# TPS54331_1A.net
KiCad netlist of a schematic drawn in Altium Designer
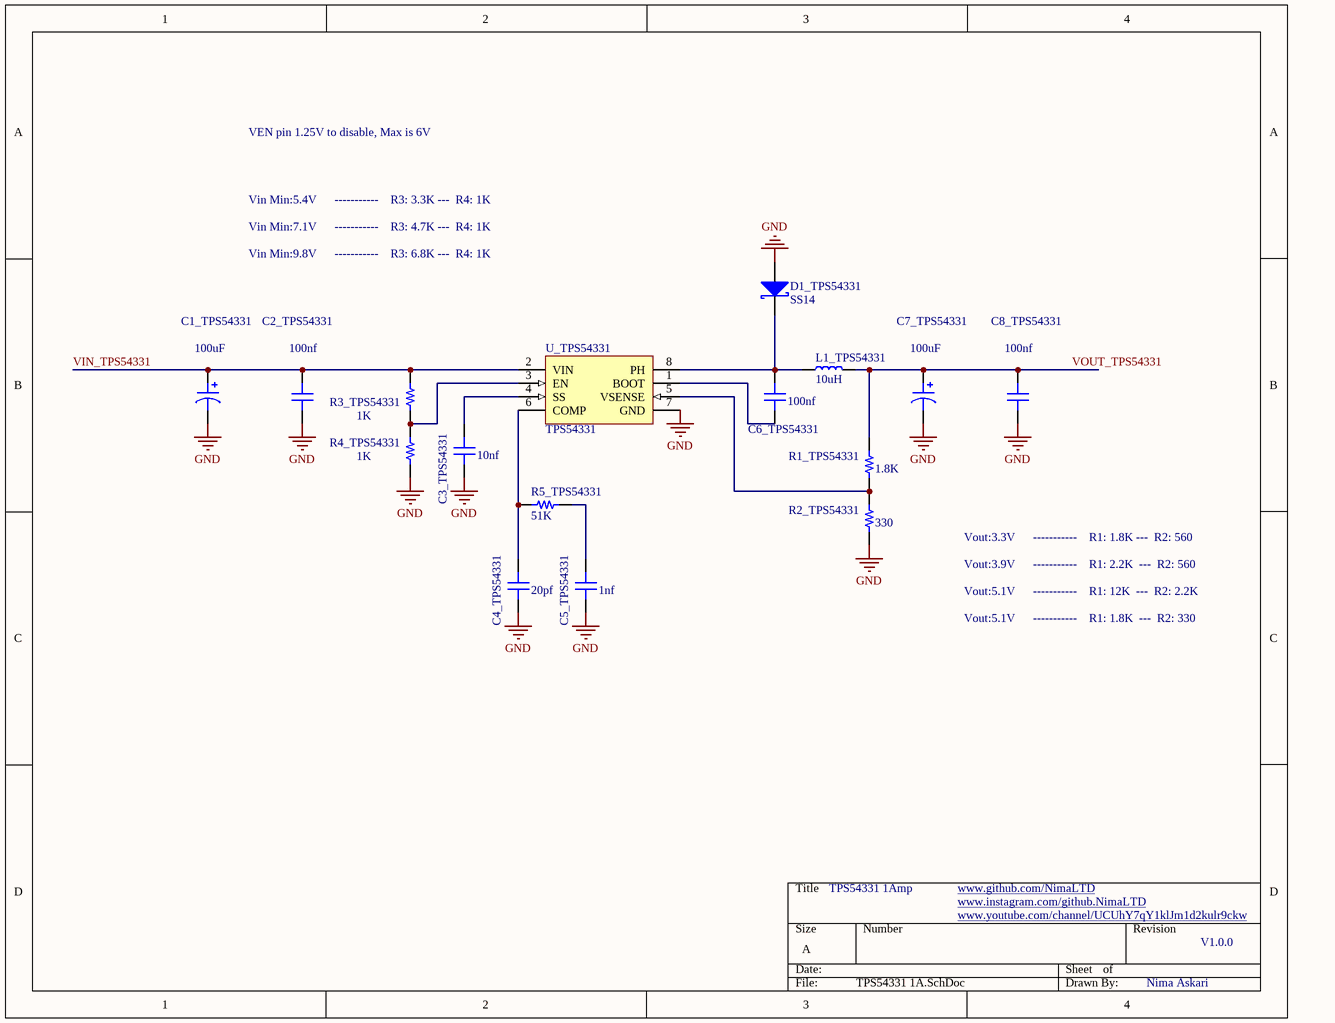
[diagram p0: TPS54331 1A.SchDoc]

(export (version "E")
  (design (tool "Eeschema 10.0.6"))
  (components
    (comp (ref "C1_TPS54331")
      (value "100uF")
      (footprint "CAP AL SMD D6 H6")
      (description "SMT Polarised Capacitor")
      (libsource (lib "CAPACITOR") (part "Pol Cap SMD AL D6 H6"))
    )
    (comp (ref "C2_TPS54331")
      (value "100nf")
      (footprint "CAP 1206")
      (description "SMT Capacitor")
      (libsource (lib "CAPACITOR") (part "Cap SMD 1206"))
    )
    (comp (ref "C3_TPS54331")
      (value "10nf")
      (footprint "CAP 0805")
      (description "SMT Capacitor")
      (libsource (lib "CAPACITOR") (part "Cap SMD 0805"))
    )
    (comp (ref "C4_TPS54331")
      (value "20pf")
      (footprint "CAP 0805")
      (description "SMT Capacitor")
      (libsource (lib "CAPACITOR") (part "Cap SMD 0805"))
    )
    (comp (ref "C5_TPS54331")
      (value "1nf")
      (footprint "CAP 0805")
      (description "SMT Capacitor")
      (libsource (lib "CAPACITOR") (part "Cap SMD 0805"))
    )
    (comp (ref "C6_TPS54331")
      (value "100nf")
      (footprint "CAP 0805")
      (description "SMT Capacitor")
      (libsource (lib "CAPACITOR") (part "Cap SMD 0805"))
    )
    (comp (ref "C7_TPS54331")
      (value "100uF")
      (footprint "CAP AL SMD D6 H6")
      (description "SMT Polarised Capacitor")
      (libsource (lib "CAPACITOR") (part "Pol Cap SMD AL D6 H6"))
    )
    (comp (ref "C8_TPS54331")
      (value "100nf")
      (footprint "CAP 0805")
      (description "SMT Capacitor")
      (libsource (lib "CAPACITOR") (part "Cap SMD 0805"))
    )
    (comp (ref "D1_TPS54331")
      (value "SS14 SMD")
      (footprint "DO214AC SMA")
      (description "1A Schottky")
      (fields (field (name "PARAMETER 1") "SS14"))
      (libsource (lib "DIODE") (part "SS14 SMD"))
    )
    (comp (ref "L1_TPS54331")
      (value "10uH")
      (footprint "IND 7X7")
      (description "SMT Inductor")
      (fields (field (name "Comment") "Inductor SMD POWER 7X7mm"))
      (libsource (lib "INDUCTOR") (part "Inductor SMD POWER 7X7mm"))
    )
    (comp (ref "R1_TPS54331")
      (value "1.8K")
      (footprint "RES 0805")
      (description "SMD Resistor")
      (libsource (lib "RESISTOR") (part "Res SMD 0805"))
    )
    (comp (ref "R2_TPS54331")
      (value "330")
      (footprint "RES 0805")
      (description "SMD Resistor")
      (libsource (lib "RESISTOR") (part "Res SMD 0805"))
    )
    (comp (ref "R3_TPS54331")
      (value "1K")
      (footprint "RES 0805")
      (description "SMD Resistor")
      (libsource (lib "RESISTOR") (part "Res SMD 0805"))
    )
    (comp (ref "R4_TPS54331")
      (value "1K")
      (footprint "RES 0805")
      (description "SMD Resistor")
      (libsource (lib "RESISTOR") (part "Res SMD 0805"))
    )
    (comp (ref "R5_TPS54331")
      (value "51K")
      (footprint "RES 0805")
      (description "SMD Resistor")
      (libsource (lib "RESISTOR") (part "Res SMD 0805"))
    )
    (comp (ref "U_TPS54331")
      (value "TPS54331")
      (footprint "SOP8")
      (fields (field (name "PARTNUMBER") "TPS54331"))
      (libsource (lib "IC") (part "TPS54331"))
    )
  )
  (nets
    (net (code "1") (name "/VIN_TPS54331") (class "Default")
      (node (ref "C1_TPS54331") (pin "1") (pinfunction "1_1") (pintype "passive"))
      (node (ref "C2_TPS54331") (pin "2") (pinfunction "2_2") (pintype "passive"))
      (node (ref "R3_TPS54331") (pin "2") (pinfunction "2_2") (pintype "passive"))
      (node (ref "U_TPS54331") (pin "2") (pinfunction "VIN_2") (pintype "power_in"))
    )
    (net (code "2") (name "/VOUT_TPS54331") (class "Default")
      (node (ref "C7_TPS54331") (pin "1") (pinfunction "1_1") (pintype "passive"))
      (node (ref "C8_TPS54331") (pin "2") (pinfunction "2_2") (pintype "passive"))
      (node (ref "L1_TPS54331") (pin "2") (pinfunction "2_2") (pintype "passive"))
      (node (ref "R1_TPS54331") (pin "2") (pinfunction "2_2") (pintype "passive"))
    )
    (net (code "3") (name "GND") (class "Default")
      (node (ref "C1_TPS54331") (pin "2") (pinfunction "2_2") (pintype "passive"))
      (node (ref "C2_TPS54331") (pin "1") (pinfunction "1_1") (pintype "passive"))
      (node (ref "C3_TPS54331") (pin "1") (pinfunction "1_1") (pintype "passive"))
      (node (ref "C4_TPS54331") (pin "1") (pinfunction "1_1") (pintype "passive"))
      (node (ref "C5_TPS54331") (pin "1") (pinfunction "1_1") (pintype "passive"))
      (node (ref "C7_TPS54331") (pin "2") (pinfunction "2_2") (pintype "passive"))
      (node (ref "C8_TPS54331") (pin "1") (pinfunction "1_1") (pintype "passive"))
      (node (ref "D1_TPS54331") (pin "1") (pinfunction "A_1") (pintype "passive"))
      (node (ref "R2_TPS54331") (pin "1") (pinfunction "1_1") (pintype "passive"))
      (node (ref "R4_TPS54331") (pin "1") (pinfunction "1_1") (pintype "passive"))
      (node (ref "U_TPS54331") (pin "7") (pinfunction "GND_7") (pintype "power_in"))
    )
    (net (code "4") (name "Net-(C5_TPS54331-Pad2)") (class "Default")
      (node (ref "C5_TPS54331") (pin "2") (pinfunction "2_2") (pintype "passive"))
      (node (ref "R5_TPS54331") (pin "1") (pinfunction "1_1") (pintype "passive"))
    )
    (net (code "5") (name "Net-(D1_TPS54331-K)") (class "Default")
      (node (ref "C6_TPS54331") (pin "2") (pinfunction "2_2") (pintype "passive"))
      (node (ref "D1_TPS54331") (pin "2") (pinfunction "K_2") (pintype "passive"))
      (node (ref "L1_TPS54331") (pin "1") (pinfunction "1_1") (pintype "passive"))
      (node (ref "U_TPS54331") (pin "8") (pinfunction "PH_8") (pintype "power_in"))
    )
    (net (code "6") (name "Net-(U_TPS54331-BOOT)") (class "Default")
      (node (ref "C6_TPS54331") (pin "1") (pinfunction "1_1") (pintype "passive"))
      (node (ref "U_TPS54331") (pin "1") (pinfunction "BOOT_1") (pintype "passive"))
    )
    (net (code "7") (name "Net-(U_TPS54331-COMP)") (class "Default")
      (node (ref "C4_TPS54331") (pin "2") (pinfunction "2_2") (pintype "passive"))
      (node (ref "R5_TPS54331") (pin "2") (pinfunction "2_2") (pintype "passive"))
      (node (ref "U_TPS54331") (pin "6") (pinfunction "COMP_6") (pintype "passive"))
    )
    (net (code "8") (name "Net-(U_TPS54331-EN)") (class "Default")
      (node (ref "R3_TPS54331") (pin "1") (pinfunction "1_1") (pintype "passive"))
      (node (ref "R4_TPS54331") (pin "2") (pinfunction "2_2") (pintype "passive"))
      (node (ref "U_TPS54331") (pin "3") (pinfunction "EN_3") (pintype "input"))
    )
    (net (code "9") (name "Net-(U_TPS54331-SS)") (class "Default")
      (node (ref "C3_TPS54331") (pin "2") (pinfunction "2_2") (pintype "passive"))
      (node (ref "U_TPS54331") (pin "4") (pinfunction "SS_4") (pintype "input"))
    )
    (net (code "10") (name "Net-(U_TPS54331-VSENSE)") (class "Default")
      (node (ref "R1_TPS54331") (pin "1") (pinfunction "1_1") (pintype "passive"))
      (node (ref "R2_TPS54331") (pin "2") (pinfunction "2_2") (pintype "passive"))
      (node (ref "U_TPS54331") (pin "5") (pinfunction "VSENSE_5") (pintype "input"))
    )
  )
)
